# untitled.net
KiCad netlist of a schematic drawn in EAGLE
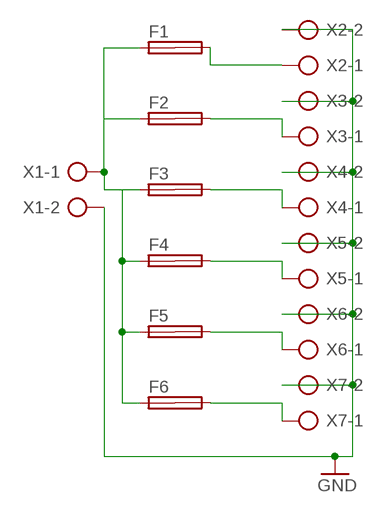
[diagram p0: schematic, sheet 1]

(export (version "E")
  (design (tool "Eeschema 10.0.6"))
  (components
    (comp (ref "F1")
      (value "SHK20Q")
      (footprint "eagle-import:SHK20Q")
      (libsource (lib "eagle-import") (part "SHK20Q"))
    )
    (comp (ref "F2")
      (value "SHK20Q")
      (footprint "eagle-import:SHK20Q")
      (libsource (lib "eagle-import") (part "SHK20Q"))
    )
    (comp (ref "F3")
      (value "SHK20Q")
      (footprint "eagle-import:SHK20Q")
      (libsource (lib "eagle-import") (part "SHK20Q"))
    )
    (comp (ref "F4")
      (value "SHK20Q")
      (footprint "eagle-import:SHK20Q")
      (libsource (lib "eagle-import") (part "SHK20Q"))
    )
    (comp (ref "F5")
      (value "SHK20Q")
      (footprint "eagle-import:SHK20Q")
      (libsource (lib "eagle-import") (part "SHK20Q"))
    )
    (comp (ref "F6")
      (value "SHK20Q")
      (footprint "eagle-import:SHK20Q")
      (libsource (lib "eagle-import") (part "SHK20Q"))
    )
    (comp (ref "X1")
      (value "AK500/2-H")
      (footprint "eagle-import:AK500_2-H")
      (libsource (lib "eagle-import") (part "AK500/2-H"))
    )
    (comp (ref "X2")
      (value "AK500/2-H")
      (footprint "eagle-import:AK500_2-H")
      (libsource (lib "eagle-import") (part "AK500/2-H"))
    )
    (comp (ref "X3")
      (value "AK500/2-H")
      (footprint "eagle-import:AK500_2-H")
      (libsource (lib "eagle-import") (part "AK500/2-H"))
    )
    (comp (ref "X4")
      (value "AK500/2-H")
      (footprint "eagle-import:AK500_2-H")
      (libsource (lib "eagle-import") (part "AK500/2-H"))
    )
    (comp (ref "X5")
      (value "AK500/2-H")
      (footprint "eagle-import:AK500_2-H")
      (libsource (lib "eagle-import") (part "AK500/2-H"))
    )
    (comp (ref "X6")
      (value "AK500/2-H")
      (footprint "eagle-import:AK500_2-H")
      (libsource (lib "eagle-import") (part "AK500/2-H"))
    )
    (comp (ref "X7")
      (value "AK500/2-H")
      (footprint "eagle-import:AK500_2-H")
      (libsource (lib "eagle-import") (part "AK500/2-H"))
    )
  )
  (nets
    (net (code "1") (name "GND") (class "Default")
      (node (ref "X1") (pin "2") (pinfunction "KL_2") (pintype "passive"))
      (node (ref "X2") (pin "2") (pinfunction "KL_2") (pintype "passive"))
      (node (ref "X3") (pin "2") (pinfunction "KL_2") (pintype "passive"))
      (node (ref "X4") (pin "2") (pinfunction "KL_2") (pintype "passive"))
      (node (ref "X5") (pin "2") (pinfunction "KL_2") (pintype "passive"))
      (node (ref "X6") (pin "2") (pinfunction "KL_2") (pintype "passive"))
      (node (ref "X7") (pin "2") (pinfunction "KL_2") (pintype "passive"))
    )
    (net (code "2") (name "Net-(X1A-KL)") (class "Default")
      (node (ref "F1") (pin "1A") (pinfunction "1A_1A") (pintype "passive"))
      (node (ref "F2") (pin "1A") (pinfunction "1A_1A") (pintype "passive"))
      (node (ref "F3") (pin "1A") (pinfunction "1A_1A") (pintype "passive"))
      (node (ref "F4") (pin "1A") (pinfunction "1A_1A") (pintype "passive"))
      (node (ref "F5") (pin "1A") (pinfunction "1A_1A") (pintype "passive"))
      (node (ref "F6") (pin "1A") (pinfunction "1A_1A") (pintype "passive"))
      (node (ref "X1") (pin "1") (pinfunction "KL_1") (pintype "passive"))
    )
    (net (code "3") (name "Net-(X2A-KL)") (class "Default")
      (node (ref "F1") (pin "2A") (pinfunction "2A_2A") (pintype "passive"))
      (node (ref "X2") (pin "1") (pinfunction "KL_1") (pintype "passive"))
    )
    (net (code "4") (name "Net-(X3A-KL)") (class "Default")
      (node (ref "F2") (pin "2A") (pinfunction "2A_2A") (pintype "passive"))
      (node (ref "X3") (pin "1") (pinfunction "KL_1") (pintype "passive"))
    )
    (net (code "5") (name "Net-(X4A-KL)") (class "Default")
      (node (ref "F3") (pin "2A") (pinfunction "2A_2A") (pintype "passive"))
      (node (ref "X4") (pin "1") (pinfunction "KL_1") (pintype "passive"))
    )
    (net (code "6") (name "Net-(X5A-KL)") (class "Default")
      (node (ref "F4") (pin "2A") (pinfunction "2A_2A") (pintype "passive"))
      (node (ref "X5") (pin "1") (pinfunction "KL_1") (pintype "passive"))
    )
    (net (code "7") (name "Net-(X6A-KL)") (class "Default")
      (node (ref "F5") (pin "2A") (pinfunction "2A_2A") (pintype "passive"))
      (node (ref "X6") (pin "1") (pinfunction "KL_1") (pintype "passive"))
    )
    (net (code "8") (name "Net-(X7A-KL)") (class "Default")
      (node (ref "F6") (pin "2A") (pinfunction "2A_2A") (pintype "passive"))
      (node (ref "X7") (pin "1") (pinfunction "KL_1") (pintype "passive"))
    )
    (net (code "9") (name "unconnected-(F1-Pad1B)") (class "Default")
      (node (ref "F1") (pin "1B") (pinfunction "1B_1B") (pintype "passive"))
    )
    (net (code "10") (name "unconnected-(F1-Pad2B)") (class "Default")
      (node (ref "F1") (pin "2B") (pinfunction "2B_2B") (pintype "passive"))
    )
    (net (code "11") (name "unconnected-(F2-Pad1B)") (class "Default")
      (node (ref "F2") (pin "1B") (pinfunction "1B_1B") (pintype "passive"))
    )
    (net (code "12") (name "unconnected-(F2-Pad2B)") (class "Default")
      (node (ref "F2") (pin "2B") (pinfunction "2B_2B") (pintype "passive"))
    )
    (net (code "13") (name "unconnected-(F3-Pad1B)") (class "Default")
      (node (ref "F3") (pin "1B") (pinfunction "1B_1B") (pintype "passive"))
    )
    (net (code "14") (name "unconnected-(F3-Pad2B)") (class "Default")
      (node (ref "F3") (pin "2B") (pinfunction "2B_2B") (pintype "passive"))
    )
    (net (code "15") (name "unconnected-(F4-Pad1B)") (class "Default")
      (node (ref "F4") (pin "1B") (pinfunction "1B_1B") (pintype "passive"))
    )
    (net (code "16") (name "unconnected-(F4-Pad2B)") (class "Default")
      (node (ref "F4") (pin "2B") (pinfunction "2B_2B") (pintype "passive"))
    )
    (net (code "17") (name "unconnected-(F5-Pad1B)") (class "Default")
      (node (ref "F5") (pin "1B") (pinfunction "1B_1B") (pintype "passive"))
    )
    (net (code "18") (name "unconnected-(F5-Pad2B)") (class "Default")
      (node (ref "F5") (pin "2B") (pinfunction "2B_2B") (pintype "passive"))
    )
    (net (code "19") (name "unconnected-(F6-Pad1B)") (class "Default")
      (node (ref "F6") (pin "1B") (pinfunction "1B_1B") (pintype "passive"))
    )
    (net (code "20") (name "unconnected-(F6-Pad2B)") (class "Default")
      (node (ref "F6") (pin "2B") (pinfunction "2B_2B") (pintype "passive"))
    )
  )
)
